# SCH_Gardening_System_Monitor_2021-09-22.net
KiCad netlist of a schematic drawn in EasyEDA
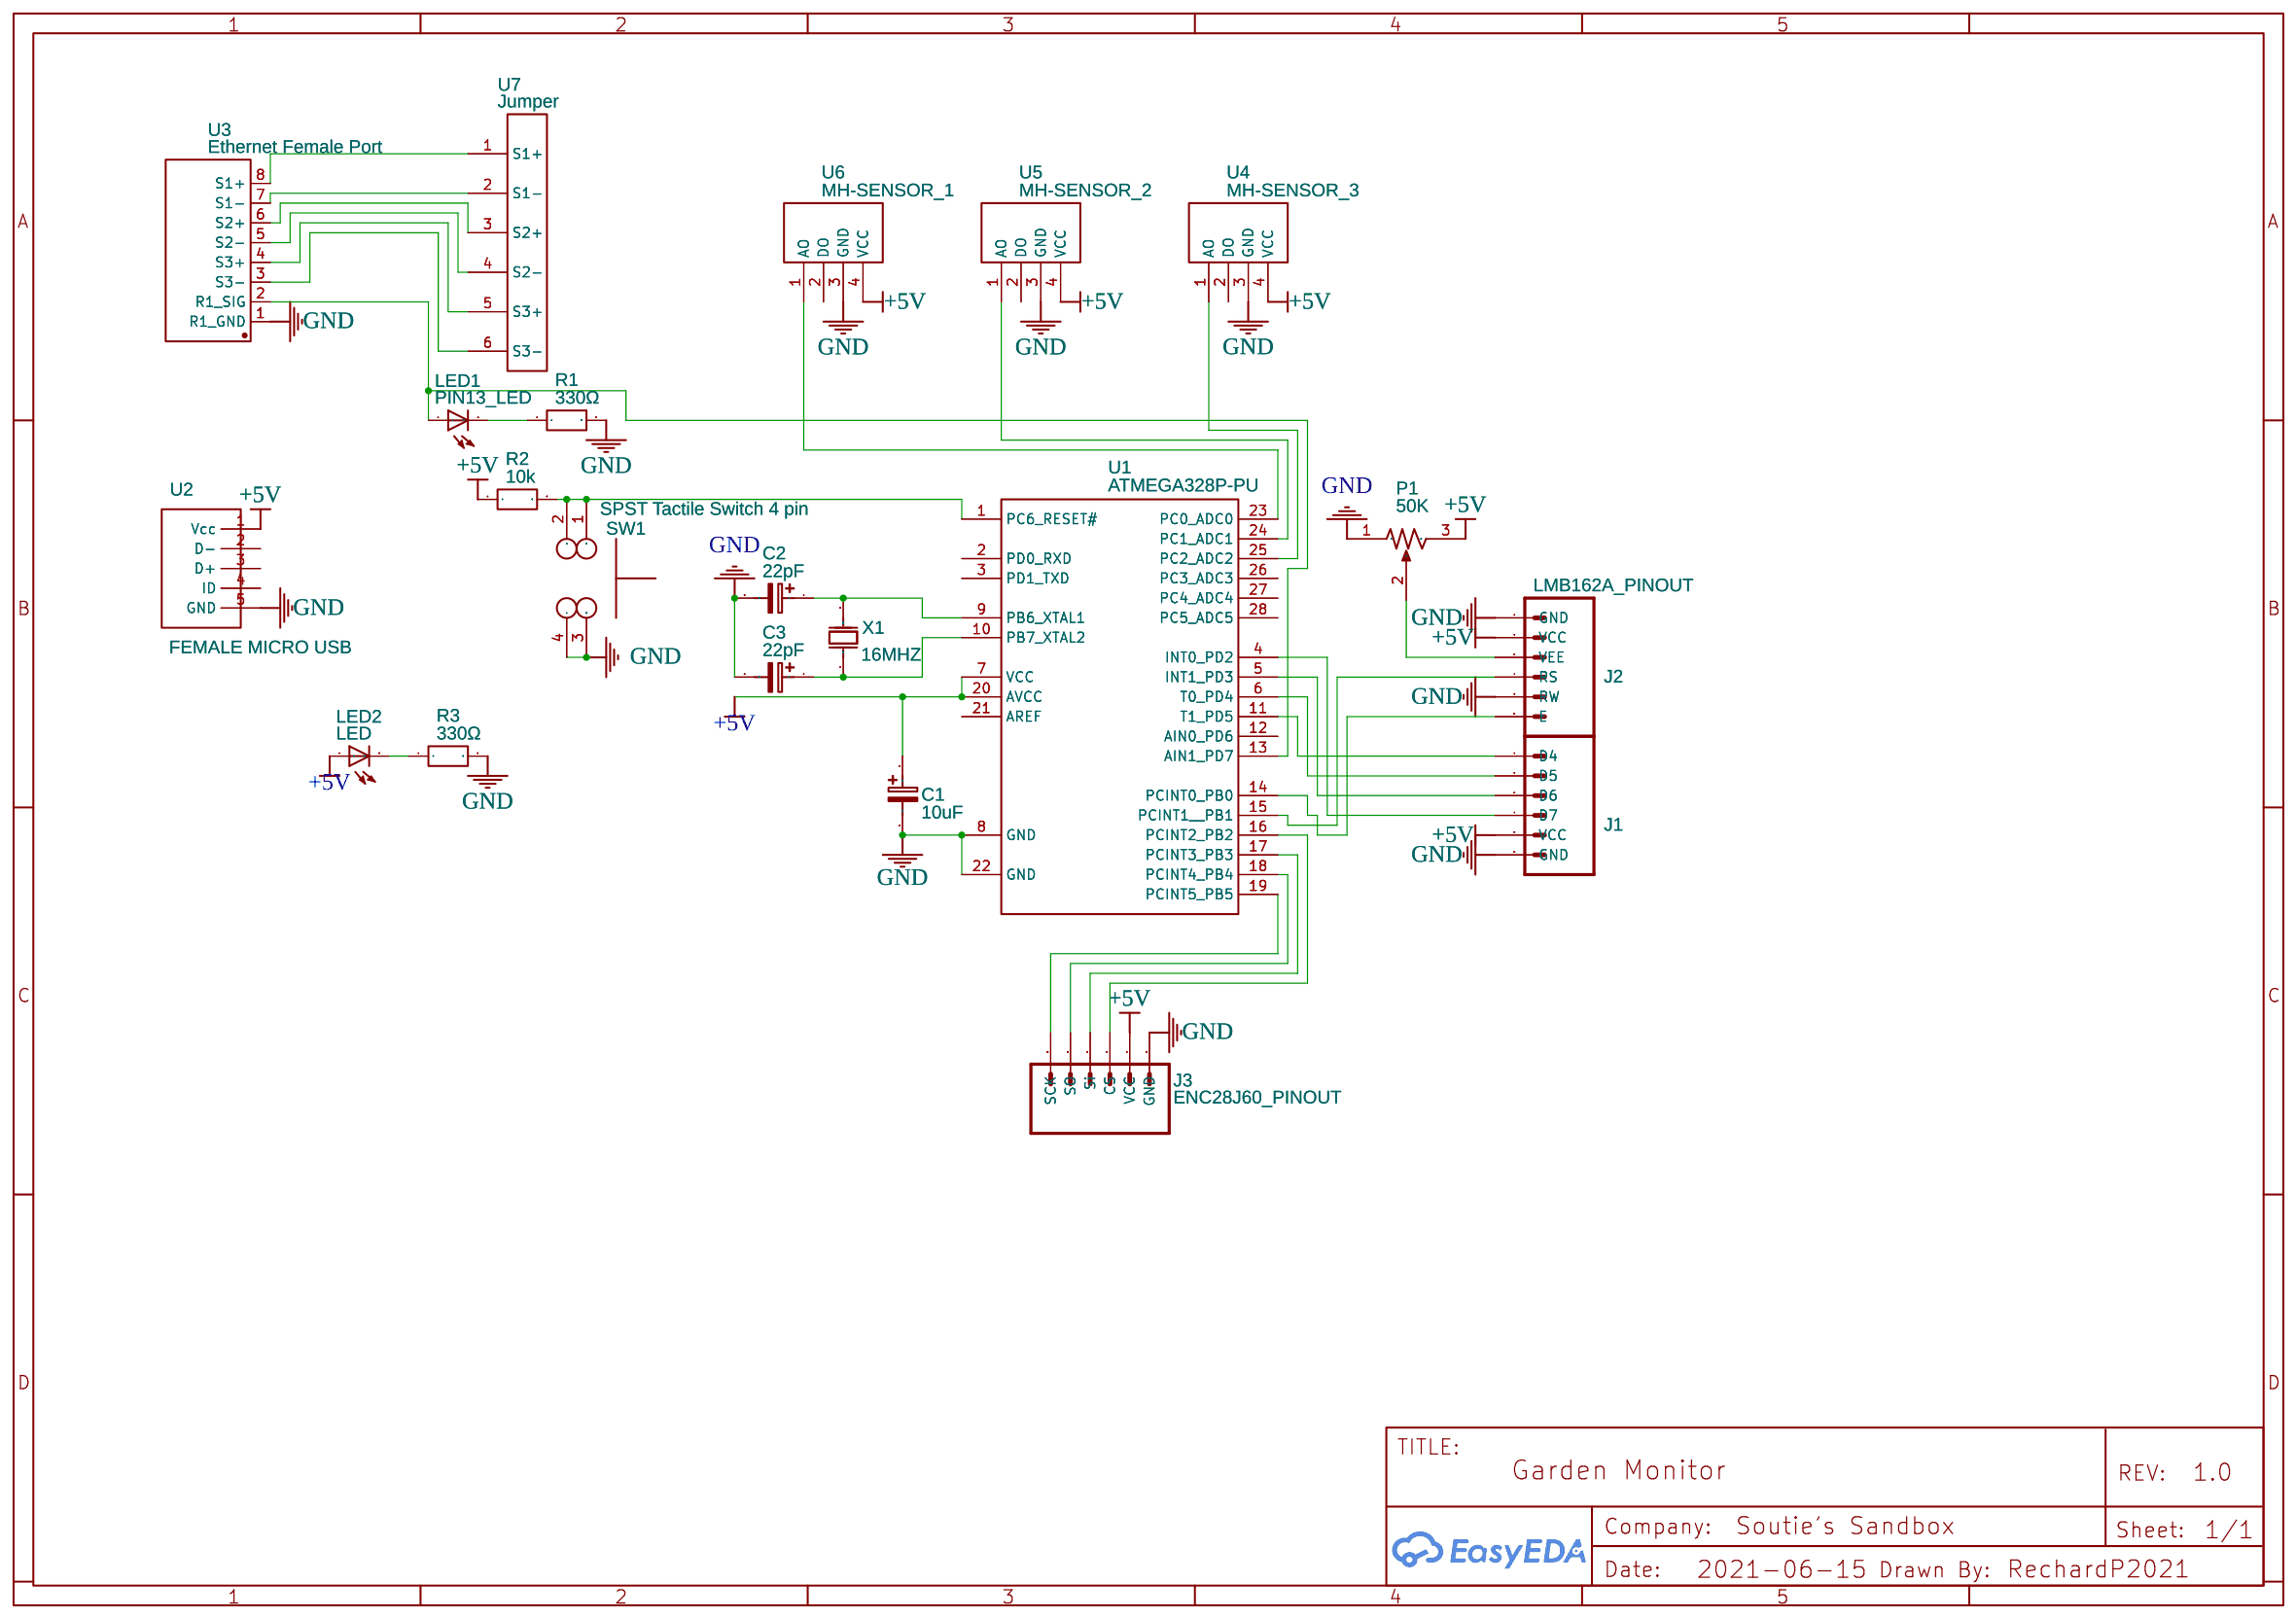
[diagram p0: schematic sheet]

(export (version "E")
  (design (tool "Eeschema 10.0.6"))
  (components
    (comp (ref "C1") (value "10uF") (libsource (lib "") (part "Capacitor")))
    (comp (ref "C2") (value "22pF") (libsource (lib "") (part "Capacitor_2")))
    (comp (ref "C3") (value "22pF") (libsource (lib "") (part "Capacitor_1")))
    (comp (ref "J1") (value "6_PIN_SERIAL_TARGET") (libsource (lib "") (part "6_PIN_SERIAL_TARGET_2")))
    (comp (ref "J2") (value "LMB162A_PINOUT") (libsource (lib "") (part "6_PIN_SERIAL_TARGET")))
    (comp (ref "J3") (value "ENC28J60_PINOUT") (libsource (lib "") (part "6_PIN_SERIAL_TARGET_1")))
    (comp (ref "LED1") (value "PIN13_LED") (libsource (lib "") (part "LED")))
    (comp (ref "LED2") (value "LED") (libsource (lib "") (part "LED")))
    (comp (ref "P1")
      (value "50K")
      (fields (field (name "BOM_Manufacturer Part") "pote 50k"))
      (libsource (lib "") (part "pote 50k"))
    )
    (comp (ref "R1")
      (value "330Ω")
      (fields
        (field (name "BOM_Manufacturer Part") "MF1/2W-100KΩ±1%T52")
        (field (name "BOM_Supplier Part") "C714085")
      )
      (libsource (lib "") (part "RESISTOR"))
    )
    (comp (ref "R2")
      (value "10k")
      (fields
        (field (name "BOM_Manufacturer Part") "MF1/2W-100KΩ±1%T52")
        (field (name "BOM_Supplier Part") "C714085")
      )
      (libsource (lib "") (part "RESISTOR"))
    )
    (comp (ref "R3")
      (value "330Ω")
      (fields
        (field (name "BOM_Manufacturer Part") "MF1/2W-100KΩ±1%T52")
        (field (name "BOM_Supplier Part") "C714085")
      )
      (libsource (lib "") (part "RESISTOR"))
    )
    (comp (ref "SW1")
      (value "SPST Tactile Switch 4 pin")
      (fields (field (name "BOM_Manufacturer Part") "C13828"))
      (libsource (lib "") (part "SPST Tactile Switch 4 pin"))
    )
    (comp (ref "U1")
      (value "ATMEGA328P-PU")
      (fields (field (name "BOM_Supplier Part") "C33901"))
      (libsource (lib "") (part "ATMEGA328P-PU"))
    )
    (comp (ref "U2")
      (value "FEMALE MICRO USB")
      (fields (field (name "BOM_Supplier Part") "C40953"))
      (libsource (lib "") (part "FEMALE MICRO USB"))
    )
    (comp (ref "U3") (value "Ethernet Female Port") (libsource (lib "") (part "Ethernet Female Port")))
    (comp (ref "U4")
      (value "MH-SENSOR_3")
      (fields (field (name "BOM_Manufacturer Part") "pin"))
      (libsource (lib "") (part "SCREEN PINS"))
    )
    (comp (ref "U5")
      (value "MH-SENSOR_2")
      (fields (field (name "BOM_Manufacturer Part") "pin"))
      (libsource (lib "") (part "SCREEN PINS"))
    )
    (comp (ref "U6")
      (value "MH-SENSOR_1")
      (fields (field (name "BOM_Manufacturer Part") "pin"))
      (libsource (lib "") (part "SCREEN PINS"))
    )
    (comp (ref "U7")
      (value "Jumper")
      (fields (field (name "BOM_Manufacturer Part") "pin3"))
      (libsource (lib "") (part "pin6"))
    )
    (comp (ref "X1")
      (value "16MHZ")
      (fields
        (field (name "BOM_Manufacturer Part") "X49SD16MSD2SC")
        (field (name "BOM_Supplier Part") "C16212")
      )
      (libsource (lib "") (part "16MHZ"))
    )
  )
  (nets
    (net (code "1") (name "+5V") (class "Default")
      (node (ref "C1") (pin "1") (pinfunction "1_1") (pintype "unspecified"))
      (node (ref "J1") (pin "5") (pinfunction "VCC_5") (pintype "bidirectional"))
      (node (ref "J2") (pin "2") (pinfunction "VCC_2") (pintype "bidirectional"))
      (node (ref "J3") (pin "2") (pinfunction "VCC_2") (pintype "bidirectional"))
      (node (ref "LED2") (pin "1") (pinfunction "A_1") (pintype "bidirectional"))
      (node (ref "P1") (pin "3") (pinfunction "3_3") (pintype "unspecified"))
      (node (ref "R2") (pin "1") (pinfunction "1_1") (pintype "unspecified"))
      (node (ref "U1") (pin "20") (pinfunction "AVCC_20") (pintype "passive"))
      (node (ref "U1") (pin "7") (pinfunction "VCC_7") (pintype "passive"))
      (node (ref "U2") (pin "1") (pinfunction "Vcc_1") (pintype "unspecified"))
      (node (ref "U4") (pin "4") (pinfunction "VCC_4") (pintype "unspecified"))
      (node (ref "U5") (pin "4") (pinfunction "VCC_4") (pintype "unspecified"))
      (node (ref "U6") (pin "4") (pinfunction "VCC_4") (pintype "unspecified"))
    )
    (net (code "2") (name "GND") (class "Default")
      (node (ref "C1") (pin "2") (pinfunction "2_2") (pintype "unspecified"))
      (node (ref "C2") (pin "2") (pinfunction "2_2") (pintype "unspecified"))
      (node (ref "C3") (pin "2") (pinfunction "2_2") (pintype "unspecified"))
      (node (ref "J1") (pin "6") (pinfunction "GND_6") (pintype "bidirectional"))
      (node (ref "J2") (pin "1") (pinfunction "GND_1") (pintype "bidirectional"))
      (node (ref "J2") (pin "5") (pinfunction "RW_5") (pintype "bidirectional"))
      (node (ref "J3") (pin "1") (pinfunction "GND_1") (pintype "bidirectional"))
      (node (ref "P1") (pin "1") (pinfunction "1_1") (pintype "unspecified"))
      (node (ref "R1") (pin "2") (pinfunction "2_2") (pintype "unspecified"))
      (node (ref "R3") (pin "2") (pinfunction "2_2") (pintype "unspecified"))
      (node (ref "SW1") (pin "3") (pinfunction "3_3") (pintype "unspecified"))
      (node (ref "SW1") (pin "4") (pinfunction "4_4") (pintype "unspecified"))
      (node (ref "U1") (pin "22") (pinfunction "GND_22") (pintype "passive"))
      (node (ref "U1") (pin "8") (pinfunction "GND_8") (pintype "passive"))
      (node (ref "U2") (pin "5") (pinfunction "GND_5") (pintype "unspecified"))
      (node (ref "U3") (pin "1") (pinfunction "R1_GND_1") (pintype "unspecified"))
      (node (ref "U4") (pin "3") (pinfunction "GND_3") (pintype "unspecified"))
      (node (ref "U5") (pin "3") (pinfunction "GND_3") (pintype "unspecified"))
      (node (ref "U6") (pin "3") (pinfunction "GND_3") (pintype "unspecified"))
    )
    (net (code "3") (name "Net-(J1-D4)") (class "Default")
      (node (ref "J1") (pin "1") (pinfunction "D4_1") (pintype "bidirectional"))
      (node (ref "U1") (pin "11") (pinfunction "T1_PD5_11") (pintype "bidirectional"))
    )
    (net (code "4") (name "Net-(J1-D5)") (class "Default")
      (node (ref "J1") (pin "2") (pinfunction "D5_2") (pintype "bidirectional"))
      (node (ref "U1") (pin "6") (pinfunction "T0_PD4_6") (pintype "bidirectional"))
    )
    (net (code "5") (name "Net-(J1-D6)") (class "Default")
      (node (ref "J1") (pin "3") (pinfunction "D6_3") (pintype "bidirectional"))
      (node (ref "U1") (pin "5") (pinfunction "INT1_PD3_5") (pintype "bidirectional"))
    )
    (net (code "6") (name "Net-(J1-D7)") (class "Default")
      (node (ref "J1") (pin "4") (pinfunction "D7_4") (pintype "bidirectional"))
      (node (ref "U1") (pin "4") (pinfunction "INT0_PD2_4") (pintype "bidirectional"))
    )
    (net (code "7") (name "Net-(J2-E)") (class "Default")
      (node (ref "J2") (pin "6") (pinfunction "E_6") (pintype "bidirectional"))
      (node (ref "U1") (pin "14") (pinfunction "PCINT0_PB0_14") (pintype "bidirectional"))
    )
    (net (code "8") (name "Net-(J2-RS)") (class "Default")
      (node (ref "J2") (pin "4") (pinfunction "RS_4") (pintype "bidirectional"))
      (node (ref "U1") (pin "15") (pinfunction "PCINT1__PB1_15") (pintype "bidirectional"))
    )
    (net (code "9") (name "Net-(J2-VEE)") (class "Default")
      (node (ref "J2") (pin "3") (pinfunction "VEE_3") (pintype "bidirectional"))
      (node (ref "P1") (pin "2") (pinfunction "2_2") (pintype "unspecified"))
    )
    (net (code "10") (name "Net-(J3-CS)") (class "Default")
      (node (ref "J3") (pin "3") (pinfunction "CS_3") (pintype "bidirectional"))
      (node (ref "U1") (pin "16") (pinfunction "PCINT2_PB2_16") (pintype "bidirectional"))
    )
    (net (code "11") (name "Net-(J3-SCK)") (class "Default")
      (node (ref "J3") (pin "6") (pinfunction "SCK_6") (pintype "bidirectional"))
      (node (ref "U1") (pin "19") (pinfunction "PCINT5_PB5_19") (pintype "bidirectional"))
    )
    (net (code "12") (name "Net-(J3-SO)") (class "Default")
      (node (ref "J3") (pin "5") (pinfunction "SO_5") (pintype "bidirectional"))
      (node (ref "U1") (pin "18") (pinfunction "PCINT4_PB4_18") (pintype "bidirectional"))
    )
    (net (code "13") (name "Net-(J3-Si)") (class "Default")
      (node (ref "J3") (pin "4") (pinfunction "Si_4") (pintype "bidirectional"))
      (node (ref "U1") (pin "17") (pinfunction "PCINT3_PB3_17") (pintype "bidirectional"))
    )
    (net (code "14") (name "Net-(LED1-A)") (class "Default")
      (node (ref "LED1") (pin "1") (pinfunction "A_1") (pintype "bidirectional"))
      (node (ref "U1") (pin "13") (pinfunction "AIN1_PD7_13") (pintype "bidirectional"))
      (node (ref "U3") (pin "2") (pinfunction "R1_SIG_2") (pintype "unspecified"))
    )
    (net (code "15") (name "Net-(LED1-C)") (class "Default")
      (node (ref "LED1") (pin "2") (pinfunction "C_2") (pintype "bidirectional"))
      (node (ref "R1") (pin "1") (pinfunction "1_1") (pintype "unspecified"))
    )
    (net (code "16") (name "Net-(LED2-C)") (class "Default")
      (node (ref "LED2") (pin "2") (pinfunction "C_2") (pintype "bidirectional"))
      (node (ref "R3") (pin "1") (pinfunction "1_1") (pintype "unspecified"))
    )
    (net (code "17") (name "Net-(U1-PB6_XTAL1)") (class "Default")
      (node (ref "C2") (pin "1") (pinfunction "1_1") (pintype "unspecified"))
      (node (ref "U1") (pin "9") (pinfunction "PB6_XTAL1_9") (pintype "bidirectional"))
      (node (ref "X1") (pin "2") (pinfunction "OSC2_2") (pintype "input"))
    )
    (net (code "18") (name "Net-(U1-PB7_XTAL2)") (class "Default")
      (node (ref "C3") (pin "1") (pinfunction "1_1") (pintype "unspecified"))
      (node (ref "U1") (pin "10") (pinfunction "PB7_XTAL2_10") (pintype "bidirectional"))
      (node (ref "X1") (pin "1") (pinfunction "OSC1_1") (pintype "input"))
    )
    (net (code "19") (name "Net-(U1-PC0_ADC0)") (class "Default")
      (node (ref "U1") (pin "23") (pinfunction "PC0_ADC0_23") (pintype "bidirectional"))
      (node (ref "U6") (pin "1") (pinfunction "AO_1") (pintype "unspecified"))
    )
    (net (code "20") (name "Net-(U1-PC1_ADC1)") (class "Default")
      (node (ref "U1") (pin "24") (pinfunction "PC1_ADC1_24") (pintype "bidirectional"))
      (node (ref "U5") (pin "1") (pinfunction "AO_1") (pintype "unspecified"))
    )
    (net (code "21") (name "Net-(U1-PC2_ADC2)") (class "Default")
      (node (ref "U1") (pin "25") (pinfunction "PC2_ADC2_25") (pintype "bidirectional"))
      (node (ref "U4") (pin "1") (pinfunction "AO_1") (pintype "unspecified"))
    )
    (net (code "22") (name "Net-(U1-PC6_RESET#)") (class "Default")
      (node (ref "R2") (pin "2") (pinfunction "2_2") (pintype "unspecified"))
      (node (ref "SW1") (pin "1") (pinfunction "1_1") (pintype "unspecified"))
      (node (ref "SW1") (pin "2") (pinfunction "2_2") (pintype "unspecified"))
      (node (ref "U1") (pin "1") (pinfunction "PC6_RESET#_1") (pintype "bidirectional"))
    )
    (net (code "23") (name "Net-(U3-S1+)") (class "Default")
      (node (ref "U3") (pin "8") (pinfunction "S1+_8") (pintype "unspecified"))
      (node (ref "U7") (pin "1") (pinfunction "S1+_1") (pintype "unspecified"))
    )
    (net (code "24") (name "Net-(U3-S1-)") (class "Default")
      (node (ref "U3") (pin "7") (pinfunction "S1-_7") (pintype "unspecified"))
      (node (ref "U7") (pin "2") (pinfunction "S1-_2") (pintype "unspecified"))
    )
    (net (code "25") (name "Net-(U3-S2+)") (class "Default")
      (node (ref "U3") (pin "6") (pinfunction "S2+_6") (pintype "unspecified"))
      (node (ref "U7") (pin "3") (pinfunction "S2+_3") (pintype "unspecified"))
    )
    (net (code "26") (name "Net-(U3-S2-)") (class "Default")
      (node (ref "U3") (pin "5") (pinfunction "S2-_5") (pintype "unspecified"))
      (node (ref "U7") (pin "4") (pinfunction "S2-_4") (pintype "unspecified"))
    )
    (net (code "27") (name "Net-(U3-S3+)") (class "Default")
      (node (ref "U3") (pin "4") (pinfunction "S3+_4") (pintype "unspecified"))
      (node (ref "U7") (pin "5") (pinfunction "S3+_5") (pintype "unspecified"))
    )
    (net (code "28") (name "Net-(U3-S3-)") (class "Default")
      (node (ref "U3") (pin "3") (pinfunction "S3-_3") (pintype "unspecified"))
      (node (ref "U7") (pin "6") (pinfunction "S3-_6") (pintype "unspecified"))
    )
    (net (code "29") (name "unconnected-(U1-AIN0_PD6-Pad12)") (class "Default")
      (node (ref "U1") (pin "12") (pinfunction "AIN0_PD6_12") (pintype "bidirectional"))
    )
    (net (code "30") (name "unconnected-(U1-AREF-Pad21)") (class "Default")
      (node (ref "U1") (pin "21") (pinfunction "AREF_21") (pintype "passive"))
    )
    (net (code "31") (name "unconnected-(U1-PC3_ADC3-Pad26)") (class "Default")
      (node (ref "U1") (pin "26") (pinfunction "PC3_ADC3_26") (pintype "bidirectional"))
    )
    (net (code "32") (name "unconnected-(U1-PC4_ADC4-Pad27)") (class "Default")
      (node (ref "U1") (pin "27") (pinfunction "PC4_ADC4_27") (pintype "bidirectional"))
    )
    (net (code "33") (name "unconnected-(U1-PC5_ADC5-Pad28)") (class "Default")
      (node (ref "U1") (pin "28") (pinfunction "PC5_ADC5_28") (pintype "bidirectional"))
    )
    (net (code "34") (name "unconnected-(U1-PD0_RXD-Pad2)") (class "Default")
      (node (ref "U1") (pin "2") (pinfunction "PD0_RXD_2") (pintype "bidirectional"))
    )
    (net (code "35") (name "unconnected-(U1-PD1_TXD-Pad3)") (class "Default")
      (node (ref "U1") (pin "3") (pinfunction "PD1_TXD_3") (pintype "bidirectional"))
    )
    (net (code "36") (name "unconnected-(U2-D+-Pad3)") (class "Default")
      (node (ref "U2") (pin "3") (pinfunction "D+_3") (pintype "unspecified"))
    )
    (net (code "37") (name "unconnected-(U2-D--Pad2)") (class "Default")
      (node (ref "U2") (pin "2") (pinfunction "D-_2") (pintype "unspecified"))
    )
    (net (code "38") (name "unconnected-(U2-ID-Pad4)") (class "Default")
      (node (ref "U2") (pin "4") (pinfunction "ID_4") (pintype "unspecified"))
    )
    (net (code "39") (name "unconnected-(U4-DO-Pad2)") (class "Default")
      (node (ref "U4") (pin "2") (pinfunction "DO_2") (pintype "unspecified"))
    )
    (net (code "40") (name "unconnected-(U5-DO-Pad2)") (class "Default")
      (node (ref "U5") (pin "2") (pinfunction "DO_2") (pintype "unspecified"))
    )
    (net (code "41") (name "unconnected-(U6-DO-Pad2)") (class "Default")
      (node (ref "U6") (pin "2") (pinfunction "DO_2") (pintype "unspecified"))
    )
  )
)
